# IO_Peripherals.net
KiCad netlist of a schematic drawn in Altium Designer
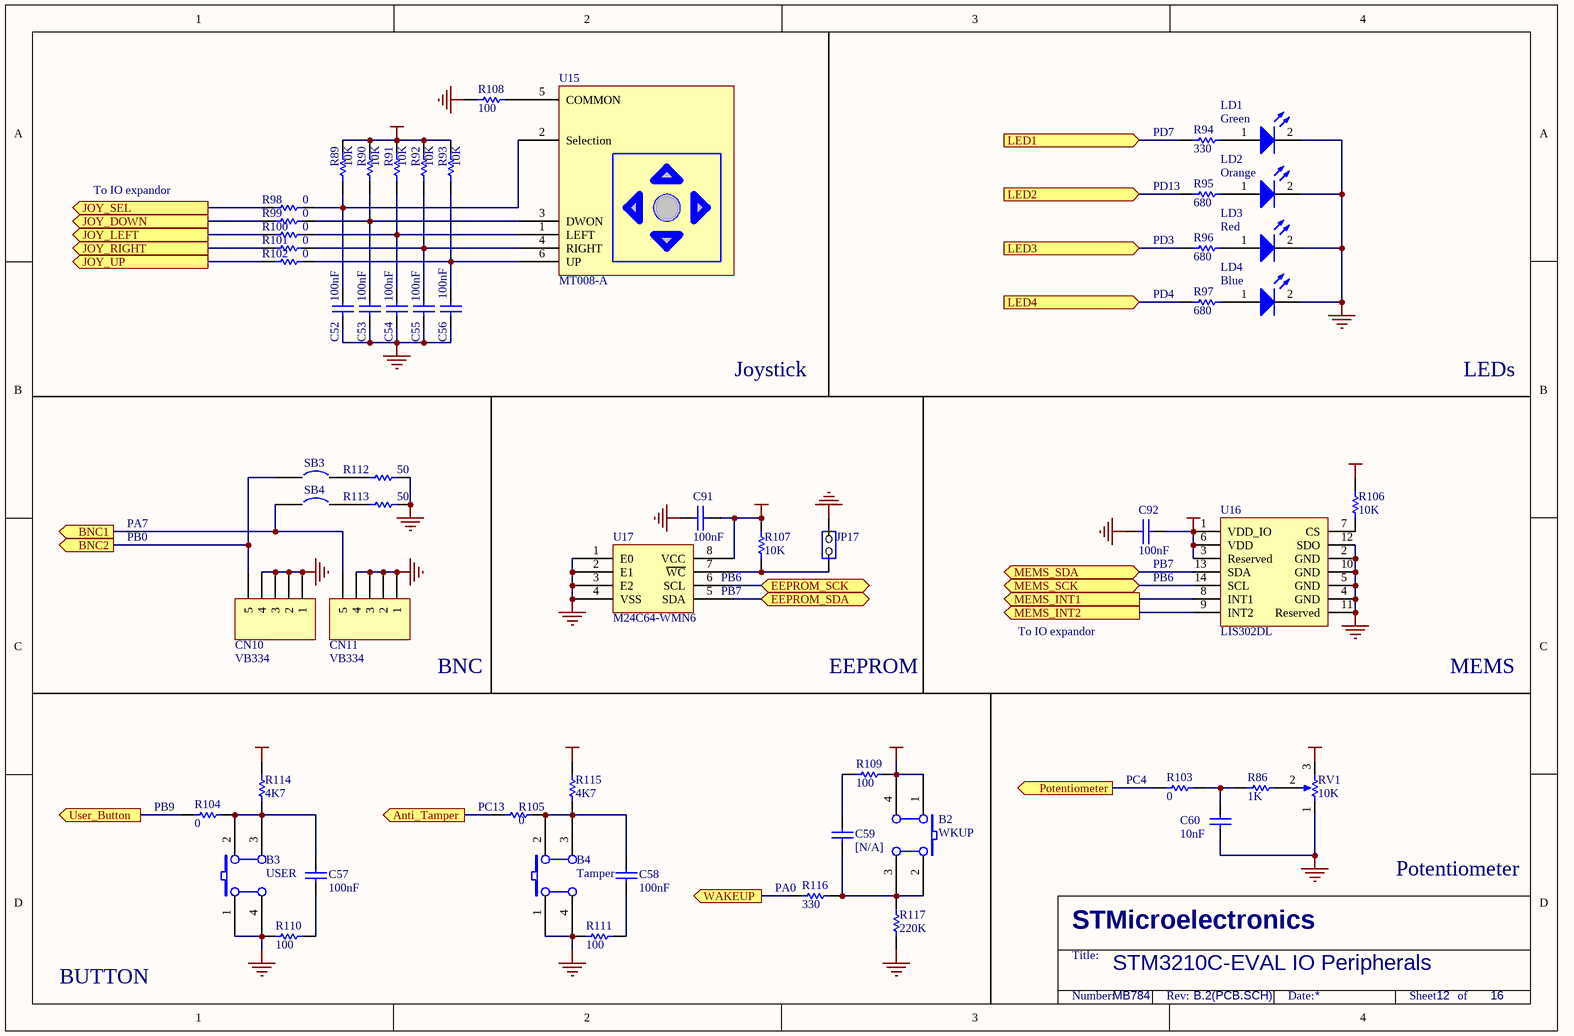
[diagram p0: IO Peripherals.SchDoc]

(export (version "E")
  (design (tool "Eeschema 10.0.6"))
  (components
    (comp (ref "B2")
      (value "WKUP")
      (footprint "PB10")
      (description "SE PUSHBUTTON")
      (libsource (lib "Documents") (part "SW PUSHBUTTON"))
    )
    (comp (ref "B3")
      (value "USER")
      (footprint "PB10")
      (description "SE PUSHBUTTON")
      (libsource (lib "Documents") (part "SW PUSHBUTTON"))
    )
    (comp (ref "B4")
      (value "Tamper")
      (footprint "PB10")
      (description "SE PUSHBUTTON")
      (libsource (lib "Documents") (part "SW PUSHBUTTON"))
    )
    (comp (ref "C52")
      (value "100nF")
      (footprint "0603C")
      (description "Capacitor")
      (fields (field (name "PUBLISHER") "Altium Limited"))
      (libsource (lib "Miscellaneous Devices") (part "CAP"))
    )
    (comp (ref "C53")
      (value "100nF")
      (footprint "0603C")
      (description "Capacitor")
      (fields (field (name "PUBLISHER") "Altium Limited"))
      (libsource (lib "Miscellaneous Devices") (part "CAP"))
    )
    (comp (ref "C54")
      (value "100nF")
      (footprint "0603C")
      (description "Capacitor")
      (fields (field (name "PUBLISHER") "Altium Limited"))
      (libsource (lib "Miscellaneous Devices") (part "CAP"))
    )
    (comp (ref "C55")
      (value "100nF")
      (footprint "0603C")
      (description "Capacitor")
      (fields (field (name "PUBLISHER") "Altium Limited"))
      (libsource (lib "Miscellaneous Devices") (part "CAP"))
    )
    (comp (ref "C56")
      (value "100nF")
      (footprint "0603C")
      (description "Capacitor")
      (fields (field (name "PUBLISHER") "Altium Limited"))
      (libsource (lib "Miscellaneous Devices") (part "CAP"))
    )
    (comp (ref "C57")
      (value "100nF")
      (footprint "0603C")
      (description "Capacitor")
      (fields (field (name "PUBLISHER") "Altium Limited"))
      (libsource (lib "Miscellaneous Devices") (part "CAP"))
    )
    (comp (ref "C58")
      (value "100nF")
      (footprint "0603C")
      (description "Capacitor")
      (fields (field (name "PUBLISHER") "Altium Limited"))
      (libsource (lib "Miscellaneous Devices") (part "CAP"))
    )
    (comp (ref "C59")
      (value "[N/A]")
      (footprint "0603C")
      (description "Capacitor")
      (fields (field (name "PUBLISHER") "Altium Limited"))
      (libsource (lib "Miscellaneous Devices") (part "CAP"))
    )
    (comp (ref "C60")
      (value "10nF")
      (footprint "0603C")
      (description "Capacitor")
      (fields (field (name "PUBLISHER") "Altium Limited"))
      (libsource (lib "Miscellaneous Devices") (part "CAP"))
    )
    (comp (ref "C91")
      (value "100nF")
      (footprint "0603C")
      (description "Capacitor")
      (libsource (lib "*") (part "CAP"))
    )
    (comp (ref "C92")
      (value "100nF")
      (footprint "0603C")
      (description "Capacitor")
      (libsource (lib "*") (part "CAP"))
    )
    (comp (ref "CN10")
      (value "VB334")
      (footprint "VB334")
      (description "Header, 5-Pin")
      (fields (field (name "PUBLISHER") "Altium Limited"))
      (libsource (lib "Miscellaneous Connectors") (part "Header 5"))
    )
    (comp (ref "CN11")
      (value "VB334")
      (footprint "VB334")
      (description "Header, 5-Pin")
      (fields (field (name "PUBLISHER") "Altium Limited"))
      (libsource (lib "Miscellaneous Connectors") (part "Header 5"))
    )
    (comp (ref "JP17") (value "~") (footprint "SIP2") (libsource (lib "*") (part "JP2")))
    (comp (ref "LD1")
      (value "Green")
      (footprint "0603D")
      (description "Typical RED, GREEN, YELLOW, AMBER GaAs LED")
      (fields (field (name "PUBLISHER") "Altium Limited"))
      (libsource (lib "Miscellaneous Devices") (part "LED2"))
    )
    (comp (ref "LD2")
      (value "Orange")
      (footprint "0603D")
      (description "Typical RED, GREEN, YELLOW, AMBER GaAs LED")
      (fields (field (name "PUBLISHER") "Altium Limited"))
      (libsource (lib "Miscellaneous Devices") (part "LED2"))
    )
    (comp (ref "LD3")
      (value "Red")
      (footprint "0603D")
      (description "Typical RED, GREEN, YELLOW, AMBER GaAs LED")
      (fields (field (name "PUBLISHER") "Altium Limited"))
      (libsource (lib "Miscellaneous Devices") (part "LED2"))
    )
    (comp (ref "LD4")
      (value "Blue")
      (footprint "0603D")
      (description "Typical RED, GREEN, YELLOW, AMBER GaAs LED")
      (fields (field (name "PUBLISHER") "Altium Limited"))
      (libsource (lib "Miscellaneous Devices") (part "LED2"))
    )
    (comp (ref "R86")
      (value "1K")
      (footprint "0603R")
      (description "Resistor")
      (fields (field (name "PUBLISHER") "Altium Limited"))
      (libsource (lib "Miscellaneous Devices") (part "Res1"))
    )
    (comp (ref "R89")
      (value "10K")
      (footprint "0603R")
      (description "Resistor")
      (fields (field (name "PUBLISHER") "Altium Limited"))
      (libsource (lib "Miscellaneous Devices") (part "Res1"))
    )
    (comp (ref "R90")
      (value "10K")
      (footprint "0603R")
      (description "Resistor")
      (fields (field (name "PUBLISHER") "Altium Limited"))
      (libsource (lib "Miscellaneous Devices") (part "Res1"))
    )
    (comp (ref "R91")
      (value "10K")
      (footprint "0603R")
      (description "Resistor")
      (fields (field (name "PUBLISHER") "Altium Limited"))
      (libsource (lib "Miscellaneous Devices") (part "Res1"))
    )
    (comp (ref "R92")
      (value "10K")
      (footprint "0603R")
      (description "Resistor")
      (fields (field (name "PUBLISHER") "Altium Limited"))
      (libsource (lib "Miscellaneous Devices") (part "Res1"))
    )
    (comp (ref "R93")
      (value "10K")
      (footprint "0603R")
      (description "Resistor")
      (fields (field (name "PUBLISHER") "Altium Limited"))
      (libsource (lib "Miscellaneous Devices") (part "Res1"))
    )
    (comp (ref "R94")
      (value "330")
      (footprint "0603R")
      (description "Resistor")
      (fields (field (name "PUBLISHER") "Altium Limited"))
      (libsource (lib "Miscellaneous Devices") (part "Res1"))
    )
    (comp (ref "R95")
      (value "680")
      (footprint "0603R")
      (description "Resistor")
      (fields (field (name "PUBLISHER") "Altium Limited"))
      (libsource (lib "Miscellaneous Devices") (part "Res1"))
    )
    (comp (ref "R96")
      (value "680")
      (footprint "0603R")
      (description "Resistor")
      (fields (field (name "PUBLISHER") "Altium Limited"))
      (libsource (lib "Miscellaneous Devices") (part "Res1"))
    )
    (comp (ref "R97")
      (value "680")
      (footprint "0603R")
      (description "Resistor")
      (fields (field (name "PUBLISHER") "Altium Limited"))
      (libsource (lib "Miscellaneous Devices") (part "Res1"))
    )
    (comp (ref "R98")
      (value "0")
      (footprint "0603R")
      (description "Resistor")
      (fields (field (name "PUBLISHER") "Altium Limited"))
      (libsource (lib "Miscellaneous Devices") (part "Res1"))
    )
    (comp (ref "R99")
      (value "0")
      (footprint "0603R")
      (description "Resistor")
      (fields (field (name "PUBLISHER") "Altium Limited"))
      (libsource (lib "Miscellaneous Devices") (part "Res1"))
    )
    (comp (ref "R100")
      (value "0")
      (footprint "0603R")
      (description "Resistor")
      (fields (field (name "PUBLISHER") "Altium Limited"))
      (libsource (lib "Miscellaneous Devices") (part "Res1"))
    )
    (comp (ref "R101")
      (value "0")
      (footprint "0603R")
      (description "Resistor")
      (fields (field (name "PUBLISHER") "Altium Limited"))
      (libsource (lib "Miscellaneous Devices") (part "Res1"))
    )
    (comp (ref "R102")
      (value "0")
      (footprint "0603R")
      (description "Resistor")
      (fields (field (name "PUBLISHER") "Altium Limited"))
      (libsource (lib "Miscellaneous Devices") (part "Res1"))
    )
    (comp (ref "R103")
      (value "0")
      (footprint "0603R")
      (description "Resistor")
      (fields (field (name "PUBLISHER") "Altium Limited"))
      (libsource (lib "Miscellaneous Devices") (part "Res1"))
    )
    (comp (ref "R104")
      (value "0")
      (footprint "0603R")
      (description "Resistor")
      (fields (field (name "PUBLISHER") "Altium Limited"))
      (libsource (lib "Miscellaneous Devices") (part "Res1"))
    )
    (comp (ref "R105")
      (value "0")
      (footprint "0603R")
      (description "Resistor")
      (fields (field (name "PUBLISHER") "Altium Limited"))
      (libsource (lib "Miscellaneous Devices") (part "Res1"))
    )
    (comp (ref "R106")
      (value "10K")
      (footprint "0603R")
      (description "Resistor")
      (fields (field (name "PUBLISHER") "Altium Limited"))
      (libsource (lib "Miscellaneous Devices") (part "res1"))
    )
    (comp (ref "R107")
      (value "10K")
      (footprint "0603R")
      (description "Resistor")
      (fields (field (name "PUBLISHER") "Altium Limited"))
      (libsource (lib "Miscellaneous Devices") (part "res1"))
    )
    (comp (ref "R108")
      (value "100")
      (footprint "0603R")
      (description "Resistor")
      (fields (field (name "PUBLISHER") "Altium Limited"))
      (libsource (lib "Miscellaneous Devices") (part "Res1"))
    )
    (comp (ref "R109")
      (value "100")
      (footprint "0603R")
      (description "Resistor")
      (fields (field (name "PUBLISHER") "Altium Limited"))
      (libsource (lib "Miscellaneous Devices") (part "Res1"))
    )
    (comp (ref "R110")
      (value "100")
      (footprint "0603R")
      (description "Resistor")
      (fields (field (name "PUBLISHER") "Altium Limited"))
      (libsource (lib "Miscellaneous Devices") (part "Res1"))
    )
    (comp (ref "R111")
      (value "100")
      (footprint "0603R")
      (description "Resistor")
      (fields (field (name "PUBLISHER") "Altium Limited"))
      (libsource (lib "Miscellaneous Devices") (part "Res1"))
    )
    (comp (ref "R112")
      (value "50")
      (footprint "0603R")
      (description "Resistor")
      (fields (field (name "PUBLISHER") "Altium Limited"))
      (libsource (lib "Miscellaneous Devices") (part "Res1"))
    )
    (comp (ref "R113")
      (value "50")
      (footprint "0603R")
      (description "Resistor")
      (fields (field (name "PUBLISHER") "Altium Limited"))
      (libsource (lib "Miscellaneous Devices") (part "Res1"))
    )
    (comp (ref "R114")
      (value "4K7")
      (footprint "0603R")
      (description "Resistor")
      (fields (field (name "PUBLISHER") "Altium Limited"))
      (libsource (lib "Miscellaneous Devices") (part "res1"))
    )
    (comp (ref "R115")
      (value "4K7")
      (footprint "0603R")
      (description "Resistor")
      (fields (field (name "PUBLISHER") "Altium Limited"))
      (libsource (lib "Miscellaneous Devices") (part "res1"))
    )
    (comp (ref "R116")
      (value "330")
      (footprint "0603R")
      (description "Resistor")
      (fields (field (name "PUBLISHER") "Altium Limited"))
      (libsource (lib "Miscellaneous Devices") (part "Res1"))
    )
    (comp (ref "R117")
      (value "220K")
      (footprint "0603R")
      (description "Resistor")
      (fields (field (name "PUBLISHER") "Altium Limited"))
      (libsource (lib "Miscellaneous Devices") (part "res1"))
    )
    (comp (ref "RV1") (value "10K") (footprint "ADJRH") (libsource (lib "STR910_SCHLIB") (part "RV")))
    (comp (ref "SB3")
      (value "~")
      (footprint "JP2_SMD")
      (description "Circuit Breaker")
      (fields (field (name "PUBLISHER") "Altium Limited"))
      (libsource (lib "Miscellaneous Devices") (part "Circuit Breaker"))
    )
    (comp (ref "SB4")
      (value "~")
      (footprint "JP2_SMD")
      (description "Circuit Breaker")
      (fields (field (name "PUBLISHER") "Altium Limited"))
      (libsource (lib "Miscellaneous Devices") (part "Circuit Breaker"))
    )
    (comp (ref "U15") (value "MT008-A") (footprint "JOY") (libsource (lib "MB513") (part "MT-008A")))
    (comp (ref "U16") (value "LIS302DL") (footprint "LGA14(3*5)") (libsource (lib "MB784") (part "LIS302DL")))
    (comp (ref "U17")
      (value "M24C64-WMN6")
      (footprint "SO8")
      (libsource (lib "ST79F5xx-EVAL") (part "M24C64-WMN6"))
    )
  )
  (nets
    (net (code "1") (name "+3V3") (class "Default")
      (node (ref "B2") (pin "1") (pinfunction "A0_1") (pintype "passive"))
      (node (ref "B2") (pin "4") (pinfunction "A1_4") (pintype "passive"))
      (node (ref "C91") (pin "2") (pinfunction "2_2") (pintype "passive"))
      (node (ref "C92") (pin "2") (pinfunction "2_2") (pintype "passive"))
      (node (ref "R106") (pin "1") (pinfunction "1_1") (pintype "passive"))
      (node (ref "R107") (pin "1") (pinfunction "1_1") (pintype "passive"))
      (node (ref "R109") (pin "1") (pinfunction "1_1") (pintype "passive"))
      (node (ref "R114") (pin "2") (pinfunction "2_2") (pintype "passive"))
      (node (ref "R115") (pin "2") (pinfunction "2_2") (pintype "passive"))
      (node (ref "R89") (pin "1") (pinfunction "1_1") (pintype "passive"))
      (node (ref "R90") (pin "2") (pinfunction "2_2") (pintype "passive"))
      (node (ref "R91") (pin "2") (pinfunction "2_2") (pintype "passive"))
      (node (ref "R92") (pin "2") (pinfunction "2_2") (pintype "passive"))
      (node (ref "R93") (pin "2") (pinfunction "2_2") (pintype "passive"))
      (node (ref "RV1") (pin "3") (pinfunction "TOP_3") (pintype "passive"))
      (node (ref "U16") (pin "1") (pinfunction "VDD_IO_1") (pintype "passive"))
      (node (ref "U16") (pin "3") (pinfunction "Reserved_3") (pintype "passive"))
      (node (ref "U16") (pin "6") (pinfunction "VDD_6") (pintype "passive"))
      (node (ref "U17") (pin "8") (pinfunction "VCC_8") (pintype "passive"))
    )
    (net (code "2") (name "/Anti_Tamper") (class "Default")
      (node (ref "R105") (pin "2") (pinfunction "2_2") (pintype "passive"))
    )
    (net (code "3") (name "/BNC1") (class "Default")
      (node (ref "CN11") (pin "5") (pinfunction "5_5") (pintype "passive"))
      (node (ref "SB4") (pin "1") (pinfunction "1_1") (pintype "passive"))
    )
    (net (code "4") (name "/BNC2") (class "Default")
      (node (ref "CN10") (pin "5") (pinfunction "5_5") (pintype "passive"))
      (node (ref "SB3") (pin "1") (pinfunction "1_1") (pintype "passive"))
    )
    (net (code "5") (name "/EEPROM_SCK") (class "Default")
      (node (ref "U17") (pin "6") (pinfunction "SCL_6") (pintype "passive"))
    )
    (net (code "6") (name "/EEPROM_SDA") (class "Default")
      (node (ref "U17") (pin "5") (pinfunction "SDA_5") (pintype "passive"))
    )
    (net (code "7") (name "/JOY_DOWN") (class "Default")
      (node (ref "R99") (pin "2") (pinfunction "2_2") (pintype "passive"))
    )
    (net (code "8") (name "/JOY_LEFT") (class "Default")
      (node (ref "R100") (pin "2") (pinfunction "2_2") (pintype "passive"))
    )
    (net (code "9") (name "/JOY_RIGHT") (class "Default")
      (node (ref "R101") (pin "2") (pinfunction "2_2") (pintype "passive"))
    )
    (net (code "10") (name "/JOY_SEL") (class "Default")
      (node (ref "R98") (pin "2") (pinfunction "2_2") (pintype "passive"))
    )
    (net (code "11") (name "/JOY_UP") (class "Default")
      (node (ref "R102") (pin "2") (pinfunction "2_2") (pintype "passive"))
    )
    (net (code "12") (name "/LED1") (class "Default")
      (node (ref "R94") (pin "2") (pinfunction "2_2") (pintype "passive"))
    )
    (net (code "13") (name "/LED2") (class "Default")
      (node (ref "R95") (pin "2") (pinfunction "2_2") (pintype "passive"))
    )
    (net (code "14") (name "/LED3") (class "Default")
      (node (ref "R96") (pin "2") (pinfunction "2_2") (pintype "passive"))
    )
    (net (code "15") (name "/LED4") (class "Default")
      (node (ref "R97") (pin "2") (pinfunction "2_2") (pintype "passive"))
    )
    (net (code "16") (name "/MEMS_INT1") (class "Default")
      (node (ref "U16") (pin "8") (pinfunction "INT1_8") (pintype "passive"))
    )
    (net (code "17") (name "/MEMS_INT2") (class "Default")
      (node (ref "U16") (pin "9") (pinfunction "INT2_9") (pintype "passive"))
    )
    (net (code "18") (name "/MEMS_SCK") (class "Default")
      (node (ref "U16") (pin "14") (pinfunction "SCL_14") (pintype "passive"))
    )
    (net (code "19") (name "/MEMS_SDA") (class "Default")
      (node (ref "U16") (pin "13") (pinfunction "SDA_13") (pintype "passive"))
    )
    (net (code "20") (name "/Potentiometer") (class "Default")
      (node (ref "R103") (pin "1") (pinfunction "1_1") (pintype "passive"))
    )
    (net (code "21") (name "/User_Button") (class "Default")
      (node (ref "R104") (pin "2") (pinfunction "2_2") (pintype "passive"))
    )
    (net (code "22") (name "/WAKEUP") (class "Default")
      (node (ref "R116") (pin "2") (pinfunction "2_2") (pintype "passive"))
    )
    (net (code "23") (name "GND") (class "Default")
      (node (ref "B3") (pin "1") (pinfunction "A0_1") (pintype "passive"))
      (node (ref "B3") (pin "4") (pinfunction "A1_4") (pintype "passive"))
      (node (ref "B4") (pin "1") (pinfunction "A0_1") (pintype "passive"))
      (node (ref "B4") (pin "4") (pinfunction "A1_4") (pintype "passive"))
      (node (ref "C52") (pin "1") (pinfunction "1_1") (pintype "passive"))
      (node (ref "C53") (pin "1") (pinfunction "1_1") (pintype "passive"))
      (node (ref "C54") (pin "1") (pinfunction "1_1") (pintype "passive"))
      (node (ref "C55") (pin "1") (pinfunction "1_1") (pintype "passive"))
      (node (ref "C56") (pin "1") (pinfunction "1_1") (pintype "passive"))
      (node (ref "C60") (pin "1") (pinfunction "1_1") (pintype "passive"))
      (node (ref "C91") (pin "1") (pinfunction "1_1") (pintype "passive"))
      (node (ref "C92") (pin "1") (pinfunction "1_1") (pintype "passive"))
      (node (ref "CN10") (pin "1") (pinfunction "1_1") (pintype "passive"))
      (node (ref "CN10") (pin "2") (pinfunction "2_2") (pintype "passive"))
      (node (ref "CN10") (pin "3") (pinfunction "3_3") (pintype "passive"))
      (node (ref "CN10") (pin "4") (pinfunction "4_4") (pintype "passive"))
      (node (ref "CN11") (pin "1") (pinfunction "1_1") (pintype "passive"))
      (node (ref "CN11") (pin "2") (pinfunction "2_2") (pintype "passive"))
      (node (ref "CN11") (pin "3") (pinfunction "3_3") (pintype "passive"))
      (node (ref "CN11") (pin "4") (pinfunction "4_4") (pintype "passive"))
      (node (ref "JP17") (pin "2") (pinfunction "NO_2") (pintype "passive"))
      (node (ref "LD1") (pin "2") (pinfunction "K_2") (pintype "passive"))
      (node (ref "LD2") (pin "2") (pinfunction "K_2") (pintype "passive"))
      (node (ref "LD3") (pin "2") (pinfunction "K_2") (pintype "passive"))
      (node (ref "LD4") (pin "2") (pinfunction "K_2") (pintype "passive"))
      (node (ref "R108") (pin "1") (pinfunction "1_1") (pintype "passive"))
      (node (ref "R110") (pin "1") (pinfunction "1_1") (pintype "passive"))
      (node (ref "R111") (pin "1") (pinfunction "1_1") (pintype "passive"))
      (node (ref "R112") (pin "2") (pinfunction "2_2") (pintype "passive"))
      (node (ref "R113") (pin "2") (pinfunction "2_2") (pintype "passive"))
      (node (ref "R117") (pin "2") (pinfunction "2_2") (pintype "passive"))
      (node (ref "RV1") (pin "1") (pinfunction "BOT_1") (pintype "passive"))
      (node (ref "U16") (pin "10") (pinfunction "GND_10") (pintype "passive"))
      (node (ref "U16") (pin "11") (pinfunction "Reserved_11") (pintype "passive"))
      (node (ref "U16") (pin "12") (pinfunction "SDO_12") (pintype "passive"))
      (node (ref "U16") (pin "2") (pinfunction "GND_2") (pintype "passive"))
      (node (ref "U16") (pin "4") (pinfunction "GND_4") (pintype "passive"))
      (node (ref "U16") (pin "5") (pinfunction "GND_5") (pintype "passive"))
      (node (ref "U17") (pin "1") (pinfunction "E0_1") (pintype "passive"))
      (node (ref "U17") (pin "2") (pinfunction "E1_2") (pintype "passive"))
      (node (ref "U17") (pin "3") (pinfunction "E2_3") (pintype "passive"))
      (node (ref "U17") (pin "4") (pinfunction "VSS_4") (pintype "passive"))
    )
    (net (code "24") (name "Net-(B2-B0)") (class "Default")
      (node (ref "B2") (pin "2") (pinfunction "B0_2") (pintype "passive"))
      (node (ref "B2") (pin "3") (pinfunction "B1_3") (pintype "passive"))
      (node (ref "C59") (pin "2") (pinfunction "2_2") (pintype "passive"))
      (node (ref "R116") (pin "1") (pinfunction "1_1") (pintype "passive"))
      (node (ref "R117") (pin "1") (pinfunction "1_1") (pintype "passive"))
    )
    (net (code "25") (name "Net-(B3-B0)") (class "Default")
      (node (ref "B3") (pin "2") (pinfunction "B0_2") (pintype "passive"))
      (node (ref "B3") (pin "3") (pinfunction "B1_3") (pintype "passive"))
      (node (ref "C57") (pin "2") (pinfunction "2_2") (pintype "passive"))
      (node (ref "R104") (pin "1") (pinfunction "1_1") (pintype "passive"))
      (node (ref "R114") (pin "1") (pinfunction "1_1") (pintype "passive"))
    )
    (net (code "26") (name "Net-(B4-B0)") (class "Default")
      (node (ref "B4") (pin "2") (pinfunction "B0_2") (pintype "passive"))
      (node (ref "B4") (pin "3") (pinfunction "B1_3") (pintype "passive"))
      (node (ref "C58") (pin "2") (pinfunction "2_2") (pintype "passive"))
      (node (ref "R105") (pin "1") (pinfunction "1_1") (pintype "passive"))
      (node (ref "R115") (pin "1") (pinfunction "1_1") (pintype "passive"))
    )
    (net (code "27") (name "Net-(C57-Pad1)") (class "Default")
      (node (ref "C57") (pin "1") (pinfunction "1_1") (pintype "passive"))
      (node (ref "R110") (pin "2") (pinfunction "2_2") (pintype "passive"))
    )
    (net (code "28") (name "Net-(C58-Pad1)") (class "Default")
      (node (ref "C58") (pin "1") (pinfunction "1_1") (pintype "passive"))
      (node (ref "R111") (pin "2") (pinfunction "2_2") (pintype "passive"))
    )
    (net (code "29") (name "Net-(C59-Pad1)") (class "Default")
      (node (ref "C59") (pin "1") (pinfunction "1_1") (pintype "passive"))
      (node (ref "R109") (pin "2") (pinfunction "2_2") (pintype "passive"))
    )
    (net (code "30") (name "Net-(C60-Pad2)") (class "Default")
      (node (ref "C60") (pin "2") (pinfunction "2_2") (pintype "passive"))
      (node (ref "R103") (pin "2") (pinfunction "2_2") (pintype "passive"))
      (node (ref "R86") (pin "1") (pinfunction "1_1") (pintype "passive"))
    )
    (net (code "31") (name "Net-(JP17-COMMON)") (class "Default")
      (node (ref "JP17") (pin "1") (pinfunction "COMMON_1") (pintype "passive"))
      (node (ref "R107") (pin "2") (pinfunction "2_2") (pintype "passive"))
      (node (ref "U17") (pin "7") (pinfunction "~{WC}_7") (pintype "passive"))
    )
    (net (code "32") (name "Net-(LD1-A)") (class "Default")
      (node (ref "LD1") (pin "1") (pinfunction "A_1") (pintype "passive"))
      (node (ref "R94") (pin "1") (pinfunction "1_1") (pintype "passive"))
    )
    (net (code "33") (name "Net-(LD2-A)") (class "Default")
      (node (ref "LD2") (pin "1") (pinfunction "A_1") (pintype "passive"))
      (node (ref "R95") (pin "1") (pinfunction "1_1") (pintype "passive"))
    )
    (net (code "34") (name "Net-(LD3-A)") (class "Default")
      (node (ref "LD3") (pin "1") (pinfunction "A_1") (pintype "passive"))
      (node (ref "R96") (pin "1") (pinfunction "1_1") (pintype "passive"))
    )
    (net (code "35") (name "Net-(LD4-A)") (class "Default")
      (node (ref "LD4") (pin "1") (pinfunction "A_1") (pintype "passive"))
      (node (ref "R97") (pin "1") (pinfunction "1_1") (pintype "passive"))
    )
    (net (code "36") (name "Net-(R112-Pad1)") (class "Default")
      (node (ref "R112") (pin "1") (pinfunction "1_1") (pintype "passive"))
      (node (ref "SB3") (pin "2") (pinfunction "2_2") (pintype "passive"))
    )
    (net (code "37") (name "Net-(R113-Pad1)") (class "Default")
      (node (ref "R113") (pin "1") (pinfunction "1_1") (pintype "passive"))
      (node (ref "SB4") (pin "2") (pinfunction "2_2") (pintype "passive"))
    )
    (net (code "38") (name "Net-(RV1-TAP)") (class "Default")
      (node (ref "R86") (pin "2") (pinfunction "2_2") (pintype "passive"))
      (node (ref "RV1") (pin "2") (pinfunction "TAP_2") (pintype "passive"))
    )
    (net (code "39") (name "Net-(U15-COMMON)") (class "Default")
      (node (ref "R108") (pin "2") (pinfunction "2_2") (pintype "passive"))
      (node (ref "U15") (pin "5") (pinfunction "COMMON_5") (pintype "passive"))
    )
    (net (code "40") (name "Net-(U15-DWON)") (class "Default")
      (node (ref "C53") (pin "2") (pinfunction "2_2") (pintype "passive"))
      (node (ref "R90") (pin "1") (pinfunction "1_1") (pintype "passive"))
      (node (ref "R99") (pin "1") (pinfunction "1_1") (pintype "passive"))
      (node (ref "U15") (pin "3") (pinfunction "DWON_3") (pintype "passive"))
    )
    (net (code "41") (name "Net-(U15-LEFT)") (class "Default")
      (node (ref "C54") (pin "2") (pinfunction "2_2") (pintype "passive"))
      (node (ref "R100") (pin "1") (pinfunction "1_1") (pintype "passive"))
      (node (ref "R91") (pin "1") (pinfunction "1_1") (pintype "passive"))
      (node (ref "U15") (pin "1") (pinfunction "LEFT_1") (pintype "passive"))
    )
    (net (code "42") (name "Net-(U15-RIGHT)") (class "Default")
      (node (ref "C55") (pin "2") (pinfunction "2_2") (pintype "passive"))
      (node (ref "R101") (pin "1") (pinfunction "1_1") (pintype "passive"))
      (node (ref "R92") (pin "1") (pinfunction "1_1") (pintype "passive"))
      (node (ref "U15") (pin "4") (pinfunction "RIGHT_4") (pintype "passive"))
    )
    (net (code "43") (name "Net-(U15-Selection)") (class "Default")
      (node (ref "C52") (pin "2") (pinfunction "2_2") (pintype "passive"))
      (node (ref "R89") (pin "2") (pinfunction "2_2") (pintype "passive"))
      (node (ref "R98") (pin "1") (pinfunction "1_1") (pintype "passive"))
      (node (ref "U15") (pin "2") (pinfunction "Selection_2") (pintype "passive"))
    )
    (net (code "44") (name "Net-(U15-UP)") (class "Default")
      (node (ref "C56") (pin "2") (pinfunction "2_2") (pintype "passive"))
      (node (ref "R102") (pin "1") (pinfunction "1_1") (pintype "passive"))
      (node (ref "R93") (pin "1") (pinfunction "1_1") (pintype "passive"))
      (node (ref "U15") (pin "6") (pinfunction "UP_6") (pintype "passive"))
    )
    (net (code "45") (name "Net-(U16-CS)") (class "Default")
      (node (ref "R106") (pin "2") (pinfunction "2_2") (pintype "passive"))
      (node (ref "U16") (pin "7") (pinfunction "CS_7") (pintype "passive"))
    )
  )
)
